# Tiny_Tetris_v1_3.net
KiCad netlist of a schematic drawn in EAGLE
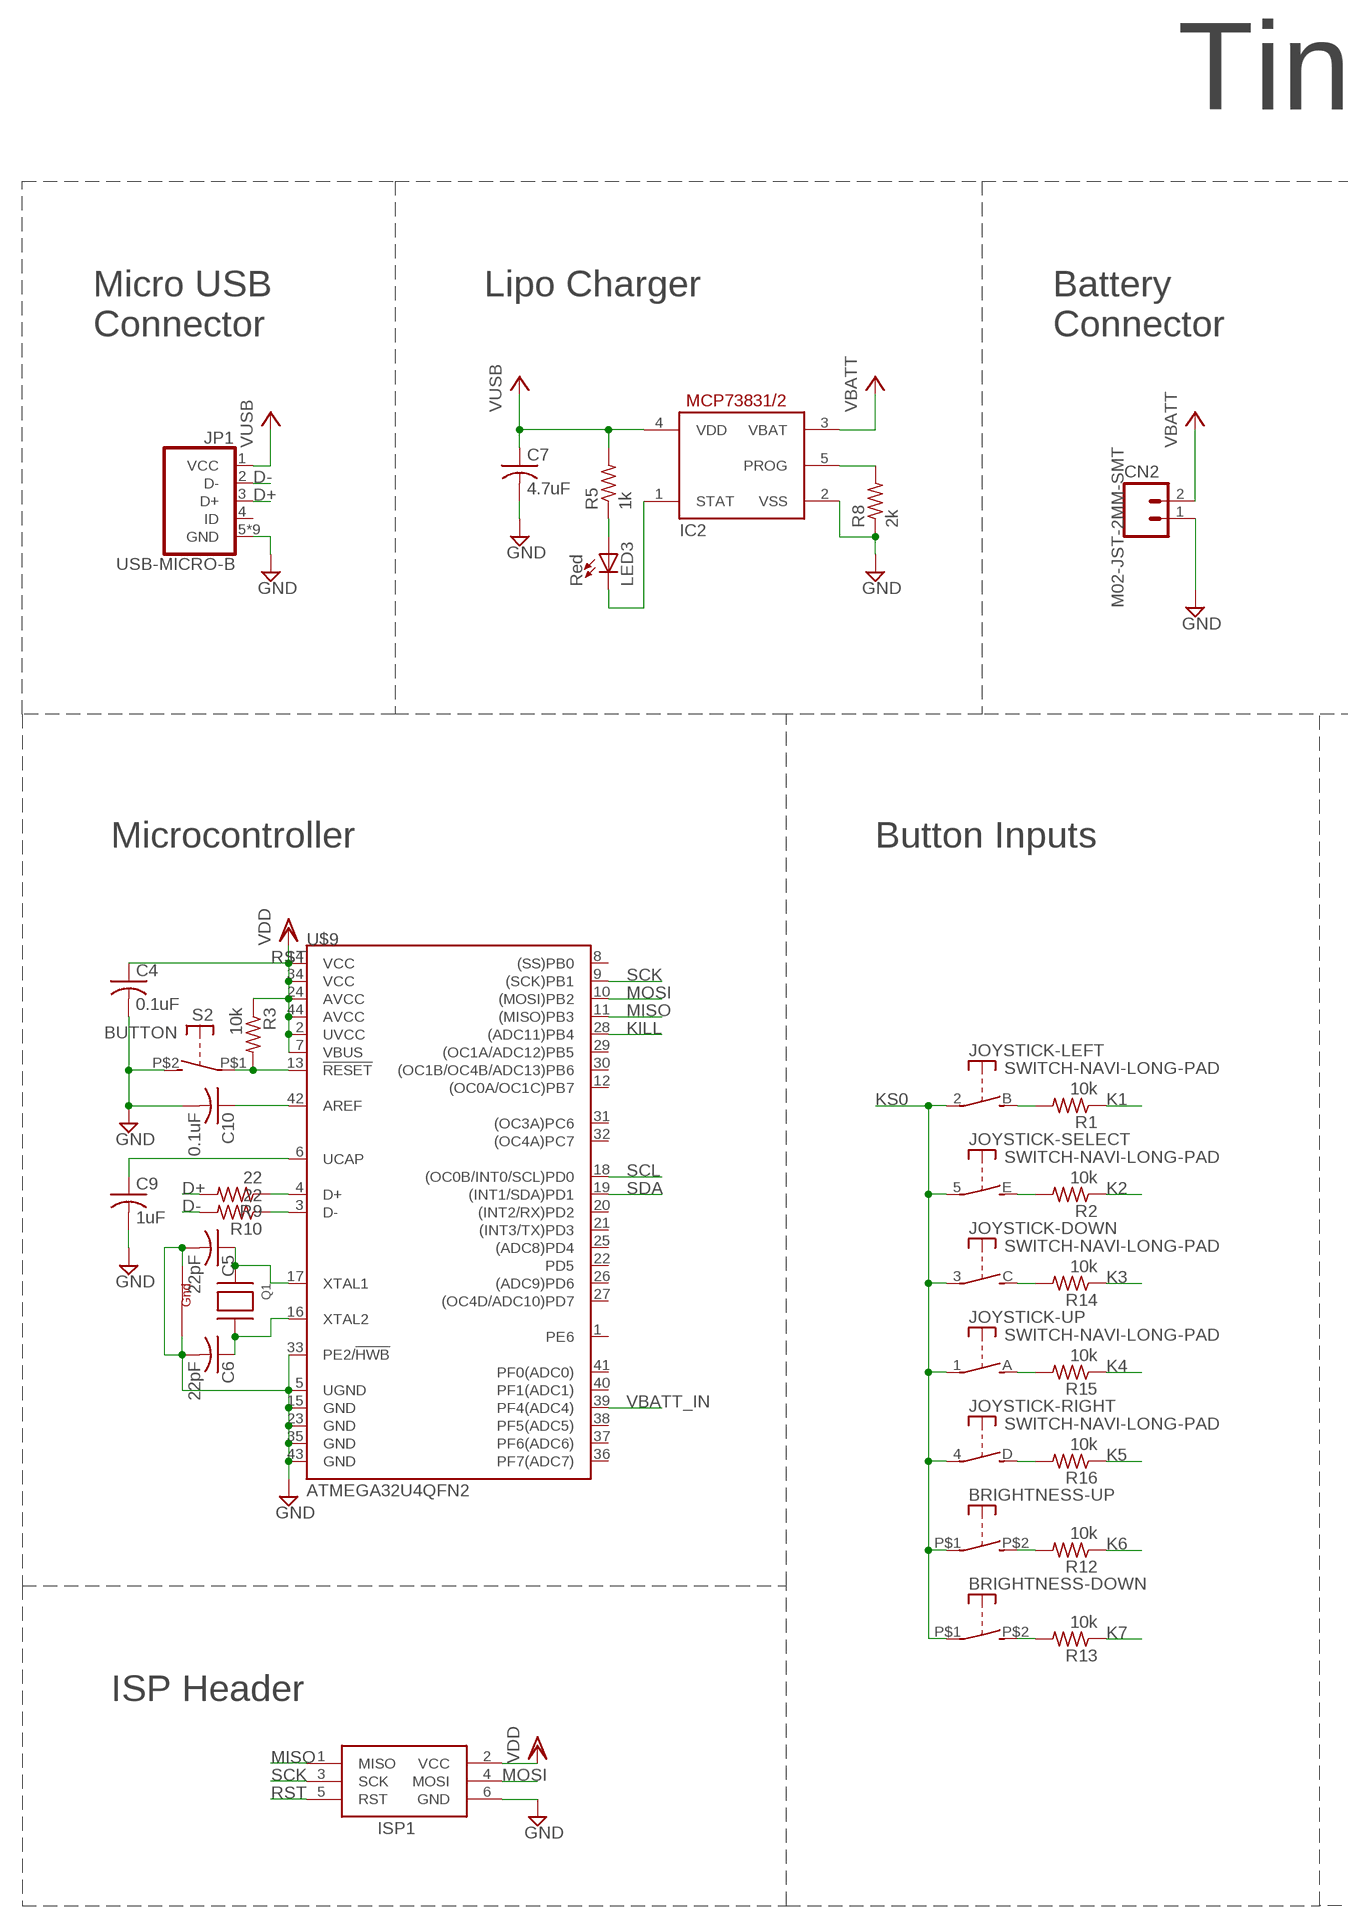
[diagram p0: schematic, sheet 1, part 1 of 2]
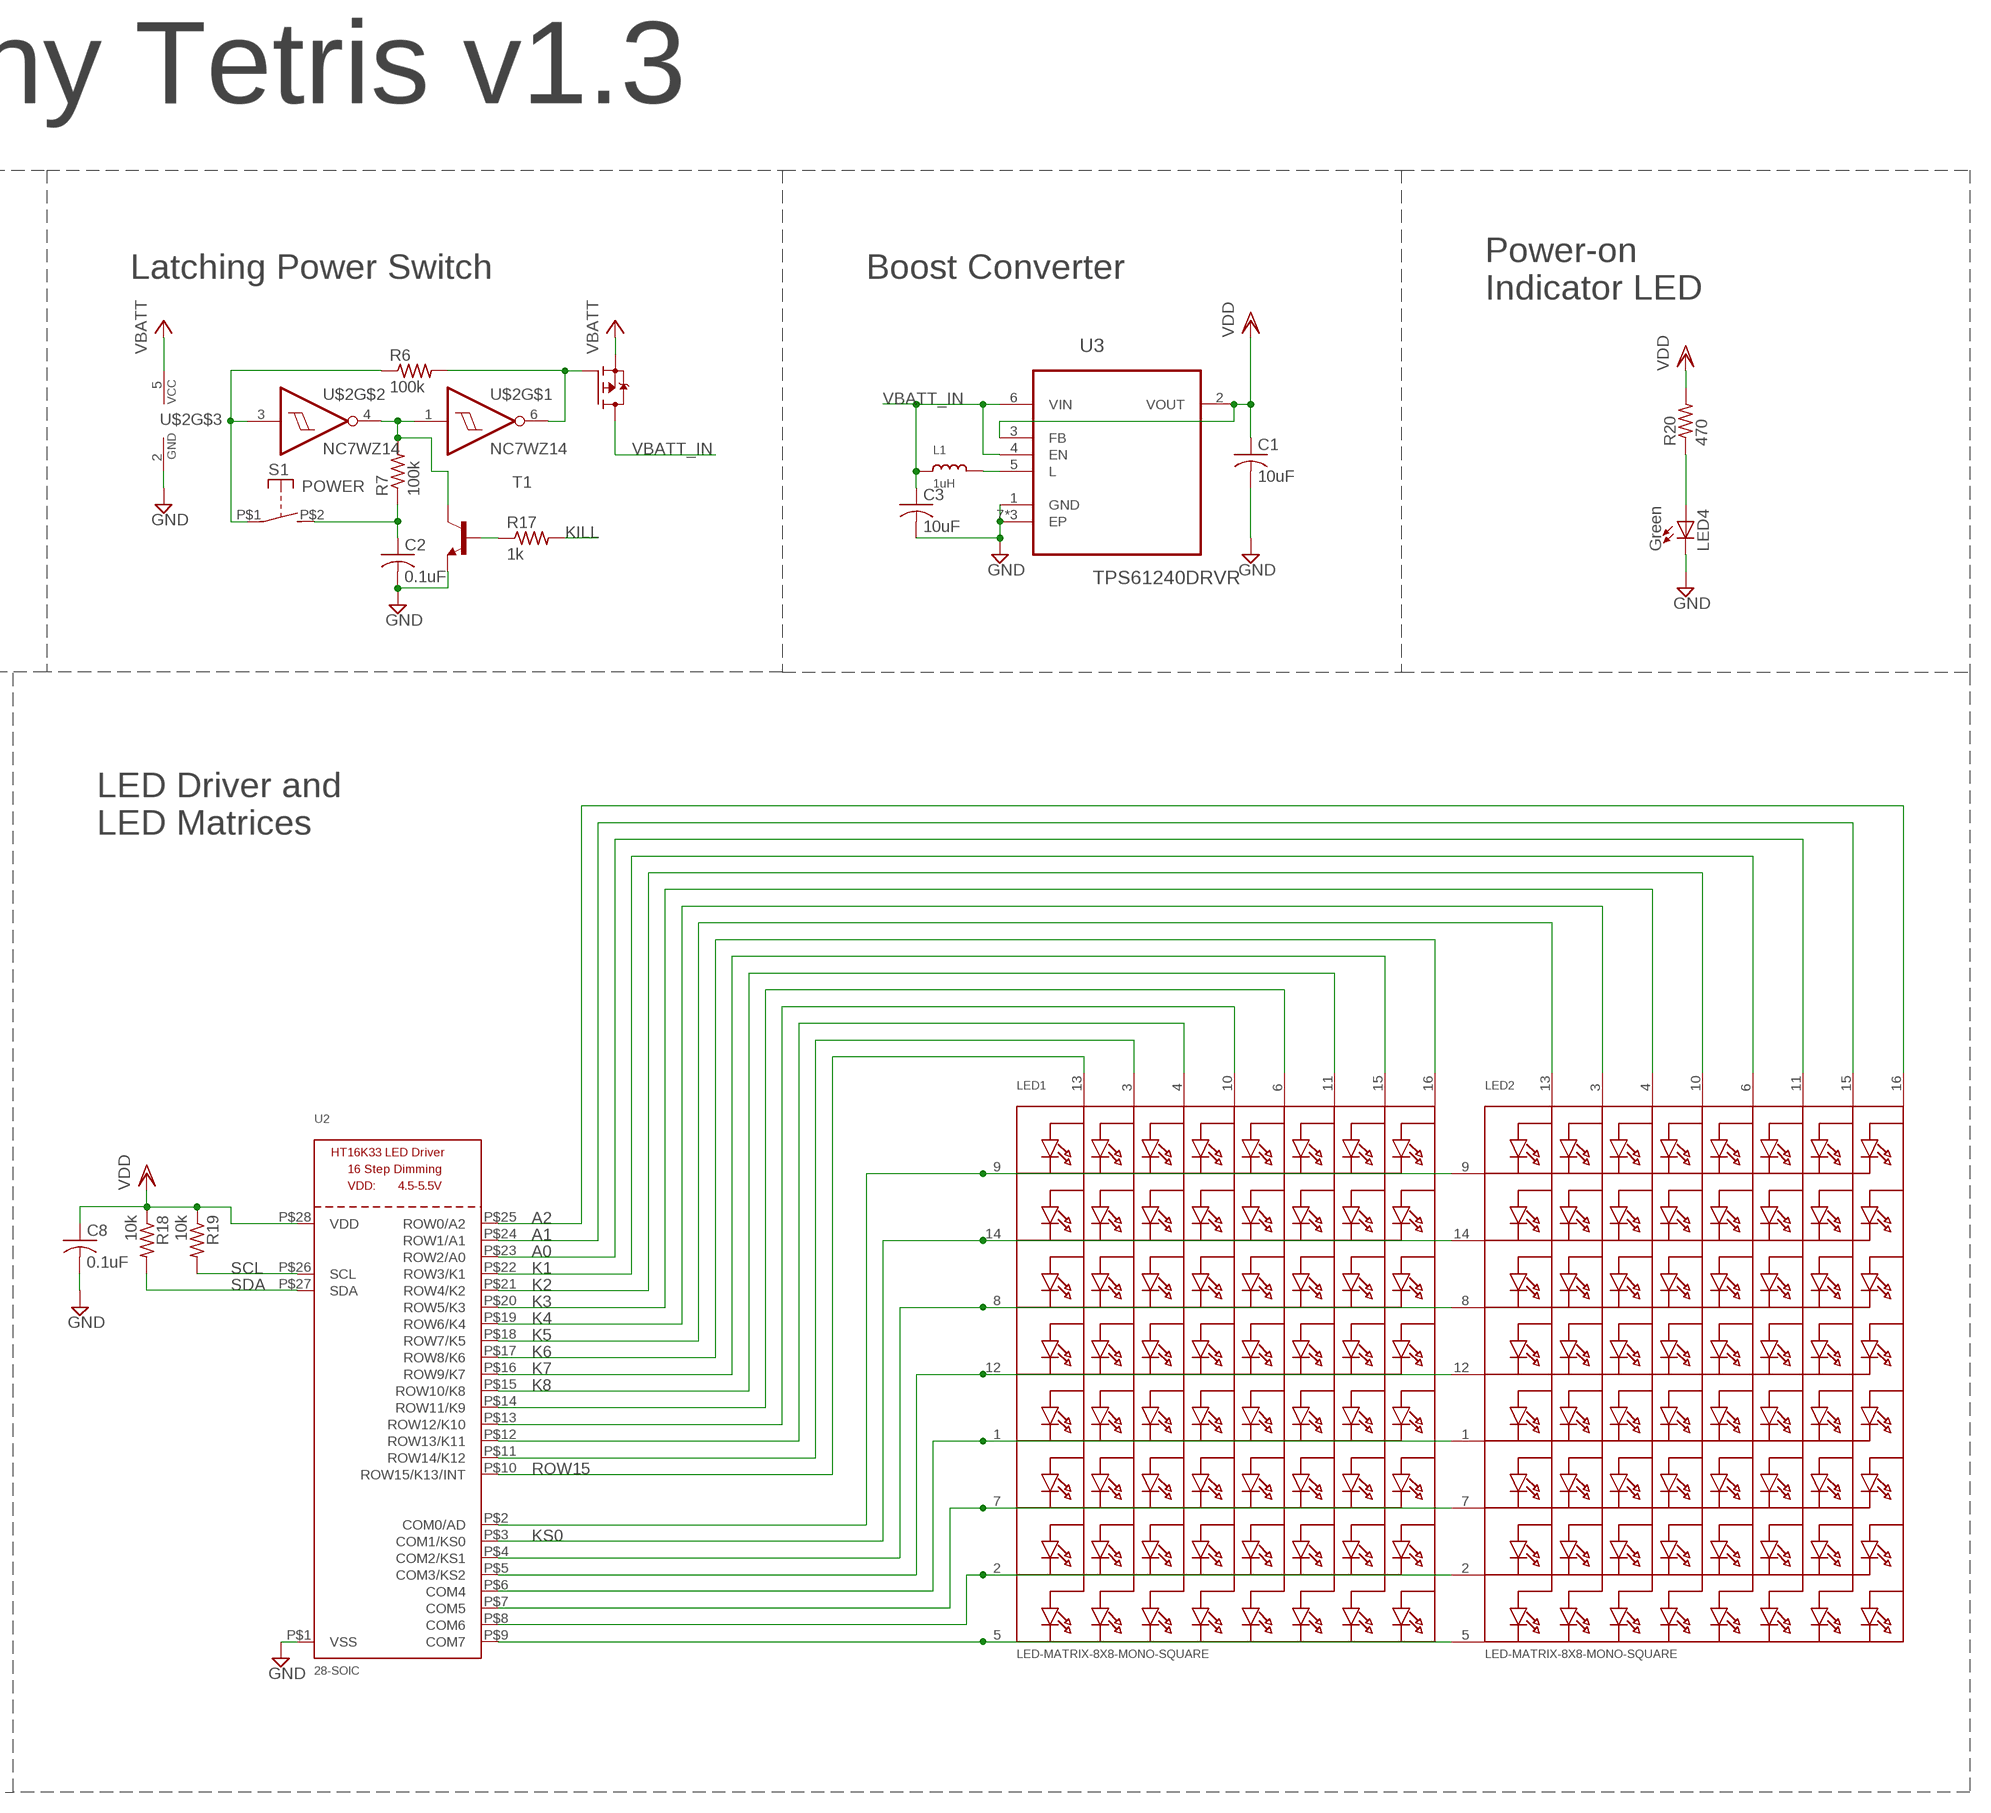
[diagram p1: schematic, sheet 1, part 2 of 2]

(export (version "E")
  (design (tool "Eeschema 10.0.6"))
  (components
    (comp (ref "BRIGHTNESS-DOWN")
      (value "SWITCH-TACTSKRELGE010")
      (footprint "eagle-import:TACT-ALPS-SKRELGE010")
      (libsource (lib "eagle-import") (part "SWITCH-TACTSKRELGE010"))
    )
    (comp (ref "BRIGHTNESS-UP")
      (value "SWITCH-TACTSKRELGE010")
      (footprint "eagle-import:TACT-ALPS-SKRELGE010")
      (libsource (lib "eagle-import") (part "SWITCH-TACTSKRELGE010"))
    )
    (comp (ref "C1")
      (value "10uF")
      (footprint "eagle-import:C0603K")
      (libsource (lib "eagle-import") (part "C-USC0603K"))
    )
    (comp (ref "C2")
      (value "0.1uF")
      (footprint "eagle-import:C0603K")
      (libsource (lib "eagle-import") (part "C-USC0603K"))
    )
    (comp (ref "C3")
      (value "10uF")
      (footprint "eagle-import:C0603K")
      (libsource (lib "eagle-import") (part "C-USC0603K"))
    )
    (comp (ref "C4")
      (value "0.1uF")
      (footprint "eagle-import:C0603K")
      (libsource (lib "eagle-import") (part "C-USC0603K"))
    )
    (comp (ref "C5")
      (value "22pF")
      (footprint "eagle-import:C0603K")
      (libsource (lib "eagle-import") (part "C-USC0603K"))
    )
    (comp (ref "C6")
      (value "22pF")
      (footprint "eagle-import:C0603K")
      (libsource (lib "eagle-import") (part "C-USC0603K"))
    )
    (comp (ref "C7")
      (value "4.7uF")
      (footprint "eagle-import:C0603K")
      (libsource (lib "eagle-import") (part "C-USC0603K"))
    )
    (comp (ref "C8")
      (value "0.1uF")
      (footprint "eagle-import:C0603K")
      (libsource (lib "eagle-import") (part "C-USC0603K"))
    )
    (comp (ref "C9")
      (value "1uF")
      (footprint "eagle-import:C0603K")
      (libsource (lib "eagle-import") (part "C-USC0603K"))
    )
    (comp (ref "C10")
      (value "0.1uF")
      (footprint "eagle-import:C0603K")
      (libsource (lib "eagle-import") (part "C-USC0603K"))
    )
    (comp (ref "CN2")
      (value "M02-JST-2MM-SMT")
      (footprint "eagle-import:1X02_NO_SILK")
      (libsource (lib "eagle-import") (part "M021X02_NO_SILK"))
    )
    (comp (ref "IC2")
      (value "MCP73831/OT")
      (footprint "eagle-import:SOT23-5L")
      (libsource (lib "eagle-import") (part "MCP73831/OT"))
    )
    (comp (ref "ISP1")
      (value "AVRISP-6")
      (footprint "eagle-import:AVRISP")
      (libsource (lib "eagle-import") (part "AVRISP-6"))
    )
    (comp (ref "JOYSTICK-")
      (value "SWITCH-NAVI-LONG-PAD")
      (footprint "eagle-import:JOYSTICK-NOKIA-3230-LONG-PAD")
      (libsource (lib "eagle-import") (part "SWITCH-NAVI-LONG-PAD"))
    )
    (comp (ref "JP1")
      (value "USB-MICRO-B")
      (footprint "eagle-import:MICRO-USB-FCI-10103594")
      (libsource (lib "eagle-import") (part "USB-MICRO-B"))
    )
    (comp (ref "L1")
      (value "1uH")
      (footprint "eagle-import:0805")
      (libsource (lib "eagle-import") (part "INDUCTOR0805"))
    )
    (comp (ref "LED1")
      (value "LED-MATRIX-8X8-MONO-SQUARE")
      (footprint "eagle-import:LED-MATRIX-8X8-MONO-SQUARE")
      (libsource (lib "eagle-import") (part "LED-MATRIX-8X8-MONO-SQUARE"))
    )
    (comp (ref "LED2")
      (value "LED-MATRIX-8X8-MONO-SQUARE")
      (footprint "eagle-import:LED-MATRIX-8X8-MONO-SQUARE")
      (libsource (lib "eagle-import") (part "LED-MATRIX-8X8-MONO-SQUARE"))
    )
    (comp (ref "LED3")
      (value "Red")
      (footprint "eagle-import:LED-0603-SIDEVIEW")
      (libsource (lib "eagle-import") (part "LED"))
    )
    (comp (ref "LED4")
      (value "Green")
      (footprint "eagle-import:LED-0603-SIDEVIEW")
      (libsource (lib "eagle-import") (part "LED"))
    )
    (comp (ref "Q1")
      (value "XTAL-4-3225")
      (footprint "eagle-import:NX3225")
      (libsource (lib "eagle-import") (part "XTAL-4-3225"))
    )
    (comp (ref "R1")
      (value "10k")
      (footprint "eagle-import:R0603")
      (libsource (lib "eagle-import") (part "R-US_R0603"))
    )
    (comp (ref "R2")
      (value "10k")
      (footprint "eagle-import:R0603")
      (libsource (lib "eagle-import") (part "R-US_R0603"))
    )
    (comp (ref "R3")
      (value "10k")
      (footprint "eagle-import:R0603")
      (libsource (lib "eagle-import") (part "R-US_R0603"))
    )
    (comp (ref "R5")
      (value "1k")
      (footprint "eagle-import:R0603")
      (libsource (lib "eagle-import") (part "R-US_R0603"))
    )
    (comp (ref "R6")
      (value "100k")
      (footprint "eagle-import:R0603")
      (libsource (lib "eagle-import") (part "R-US_R0603"))
    )
    (comp (ref "R7")
      (value "100k")
      (footprint "eagle-import:R0603")
      (libsource (lib "eagle-import") (part "R-US_R0603"))
    )
    (comp (ref "R8")
      (value "2k")
      (footprint "eagle-import:R0603")
      (libsource (lib "eagle-import") (part "R-US_R0603"))
    )
    (comp (ref "R9")
      (value "22")
      (footprint "eagle-import:R0603")
      (libsource (lib "eagle-import") (part "R-US_R0603"))
    )
    (comp (ref "R10")
      (value "22")
      (footprint "eagle-import:R0603")
      (libsource (lib "eagle-import") (part "R-US_R0603"))
    )
    (comp (ref "R12")
      (value "10k")
      (footprint "eagle-import:R0603")
      (libsource (lib "eagle-import") (part "R-US_R0603"))
    )
    (comp (ref "R13")
      (value "10k")
      (footprint "eagle-import:R0603")
      (libsource (lib "eagle-import") (part "R-US_R0603"))
    )
    (comp (ref "R14")
      (value "10k")
      (footprint "eagle-import:R0603")
      (libsource (lib "eagle-import") (part "R-US_R0603"))
    )
    (comp (ref "R15")
      (value "10k")
      (footprint "eagle-import:R0603")
      (libsource (lib "eagle-import") (part "R-US_R0603"))
    )
    (comp (ref "R16")
      (value "10k")
      (footprint "eagle-import:R0603")
      (libsource (lib "eagle-import") (part "R-US_R0603"))
    )
    (comp (ref "R17")
      (value "1k")
      (footprint "eagle-import:R0603")
      (libsource (lib "eagle-import") (part "R-US_R0603"))
    )
    (comp (ref "R18")
      (value "10k")
      (footprint "eagle-import:R0603")
      (libsource (lib "eagle-import") (part "R-US_R0603"))
    )
    (comp (ref "R19")
      (value "10k")
      (footprint "eagle-import:R0603")
      (libsource (lib "eagle-import") (part "R-US_R0603"))
    )
    (comp (ref "R20")
      (value "470")
      (footprint "eagle-import:R0603")
      (libsource (lib "eagle-import") (part "R-US_R0603"))
    )
    (comp (ref "S1")
      (value "POWER")
      (footprint "eagle-import:TACT-ALPS-SKRELGE010")
      (libsource (lib "eagle-import") (part "SWITCH-TACTSKRELGE010"))
    )
    (comp (ref "S2")
      (value "BUTTON")
      (footprint "eagle-import:TACT-ALPS-SKRELGE010")
      (libsource (lib "eagle-import") (part "SWITCH-TACTSKRELGE010"))
    )
    (comp (ref "T1")
      (value "MMBT2222ALT1-NPN-SOT23-BEC")
      (footprint "eagle-import:SOT23-BEC")
      (libsource (lib "eagle-import") (part "-NPN-SOT23-BECMMBT2222ALT1"))
    )
    (comp (ref "U$1")
      (value "IRLML6402")
      (footprint "eagle-import:SOT23")
      (libsource (lib "eagle-import") (part "IRLML6402"))
    )
    (comp (ref "U$2")
      (value "NC7WZ14")
      (footprint "eagle-import:SC-70-6")
      (libsource (lib "eagle-import") (part "NC7WZ14"))
    )
    (comp (ref "U$9")
      (value "ATMEGA32U4QFN2")
      (footprint "eagle-import:SPARKFUN-DIGITALIC_QFN-44-NOPAD")
      (libsource (lib "eagle-import") (part "ATMEGA32U4QFN2"))
    )
    (comp (ref "U2")
      (value "28-SOIC")
      (footprint "eagle-import:SOP28_300MIL")
      (libsource (lib "eagle-import") (part "HT16K33_SOP28"))
    )
    (comp (ref "U3")
      (value "TPS61240DRVR")
      (footprint "eagle-import:SON65P200X200X80-7N")
      (libsource (lib "eagle-import") (part "TPS61240DRVR"))
    )
  )
  (nets
    (net (code "1") (name "/A0") (class "Default")
      (node (ref "LED2") (pin "11") (pinfunction "A6_11") (pintype "bidirectional"))
      (node (ref "U2") (pin "P$23") (pinfunction "ROW2/A0_P$23") (pintype "bidirectional"))
    )
    (net (code "2") (name "/A1") (class "Default")
      (node (ref "LED2") (pin "15") (pinfunction "A7_15") (pintype "bidirectional"))
      (node (ref "U2") (pin "P$24") (pinfunction "ROW1/A1_P$24") (pintype "bidirectional"))
    )
    (net (code "3") (name "/A2") (class "Default")
      (node (ref "LED2") (pin "16") (pinfunction "A8_16") (pintype "bidirectional"))
      (node (ref "U2") (pin "P$25") (pinfunction "ROW0/A2_P$25") (pintype "bidirectional"))
    )
    (net (code "4") (name "/D+") (class "Default")
      (node (ref "JP1") (pin "3") (pinfunction "D+_3") (pintype "bidirectional"))
      (node (ref "R9") (pin "2") (pinfunction "2_2") (pintype "passive"))
    )
    (net (code "5") (name "/D-") (class "Default")
      (node (ref "JP1") (pin "2") (pinfunction "D-_2") (pintype "bidirectional"))
      (node (ref "R10") (pin "2") (pinfunction "2_2") (pintype "passive"))
    )
    (net (code "6") (name "/K1") (class "Default")
      (node (ref "LED2") (pin "6") (pinfunction "A5_6") (pintype "bidirectional"))
      (node (ref "R1") (pin "1") (pinfunction "1_1") (pintype "passive"))
      (node (ref "U2") (pin "P$22") (pinfunction "ROW3/K1_P$22") (pintype "bidirectional"))
    )
    (net (code "7") (name "/K2") (class "Default")
      (node (ref "LED2") (pin "10") (pinfunction "A4_10") (pintype "bidirectional"))
      (node (ref "R2") (pin "1") (pinfunction "1_1") (pintype "passive"))
      (node (ref "U2") (pin "P$21") (pinfunction "ROW4/K2_P$21") (pintype "bidirectional"))
    )
    (net (code "8") (name "/K3") (class "Default")
      (node (ref "LED2") (pin "4") (pinfunction "A3_4") (pintype "bidirectional"))
      (node (ref "R14") (pin "1") (pinfunction "1_1") (pintype "passive"))
      (node (ref "U2") (pin "P$20") (pinfunction "ROW5/K3_P$20") (pintype "bidirectional"))
    )
    (net (code "9") (name "/K4") (class "Default")
      (node (ref "LED2") (pin "3") (pinfunction "A2_3") (pintype "bidirectional"))
      (node (ref "R15") (pin "1") (pinfunction "1_1") (pintype "passive"))
      (node (ref "U2") (pin "P$19") (pinfunction "ROW6/K4_P$19") (pintype "bidirectional"))
    )
    (net (code "10") (name "/K5") (class "Default")
      (node (ref "LED2") (pin "13") (pinfunction "A1_13") (pintype "bidirectional"))
      (node (ref "R16") (pin "1") (pinfunction "1_1") (pintype "passive"))
      (node (ref "U2") (pin "P$18") (pinfunction "ROW7/K5_P$18") (pintype "bidirectional"))
    )
    (net (code "11") (name "/K6") (class "Default")
      (node (ref "LED1") (pin "16") (pinfunction "A8_16") (pintype "bidirectional"))
      (node (ref "R12") (pin "1") (pinfunction "1_1") (pintype "passive"))
      (node (ref "U2") (pin "P$17") (pinfunction "ROW8/K6_P$17") (pintype "bidirectional"))
    )
    (net (code "12") (name "/K7") (class "Default")
      (node (ref "LED1") (pin "15") (pinfunction "A7_15") (pintype "bidirectional"))
      (node (ref "R13") (pin "1") (pinfunction "1_1") (pintype "passive"))
      (node (ref "U2") (pin "P$16") (pinfunction "ROW9/K7_P$16") (pintype "bidirectional"))
    )
    (net (code "13") (name "/K8") (class "Default")
      (node (ref "LED1") (pin "11") (pinfunction "A6_11") (pintype "bidirectional"))
      (node (ref "U2") (pin "P$15") (pinfunction "ROW10/K8_P$15") (pintype "bidirectional"))
    )
    (net (code "14") (name "/KILL") (class "Default")
      (node (ref "R17") (pin "2") (pinfunction "2_2") (pintype "passive"))
      (node (ref "U$9") (pin "28") (pinfunction "(ADC11)PB4_28") (pintype "bidirectional"))
    )
    (net (code "15") (name "/KS0") (class "Default")
      (node (ref "BRIGHTNESS-DOWN") (pin "P$1") (pinfunction "P_P$1") (pintype "passive"))
      (node (ref "BRIGHTNESS-UP") (pin "P$1") (pinfunction "P_P$1") (pintype "passive"))
      (node (ref "JOYSTICK-") (pin "1") (pinfunction "P_1") (pintype "passive"))
      (node (ref "JOYSTICK-") (pin "2") (pinfunction "P_2") (pintype "passive"))
      (node (ref "JOYSTICK-") (pin "3") (pinfunction "P_3") (pintype "passive"))
      (node (ref "JOYSTICK-") (pin "4") (pinfunction "P_4") (pintype "passive"))
      (node (ref "JOYSTICK-") (pin "5") (pinfunction "P_5") (pintype "passive"))
      (node (ref "LED1") (pin "14") (pinfunction "K2_14") (pintype "bidirectional"))
      (node (ref "LED2") (pin "14") (pinfunction "K2_14") (pintype "bidirectional"))
      (node (ref "U2") (pin "P$3") (pinfunction "COM1/KS0_P$3") (pintype "bidirectional"))
    )
    (net (code "16") (name "/MISO") (class "Default")
      (node (ref "ISP1") (pin "1") (pinfunction "MISO_1") (pintype "input"))
      (node (ref "U$9") (pin "11") (pinfunction "(MISO)PB3_11") (pintype "bidirectional"))
    )
    (net (code "17") (name "/MOSI") (class "Default")
      (node (ref "ISP1") (pin "4") (pinfunction "MOSI_4") (pintype "output"))
      (node (ref "U$9") (pin "10") (pinfunction "(MOSI)PB2_10") (pintype "bidirectional"))
    )
    (net (code "18") (name "/ROW15") (class "Default")
      (node (ref "LED1") (pin "13") (pinfunction "A1_13") (pintype "bidirectional"))
      (node (ref "U2") (pin "P$10") (pinfunction "ROW15/K13/INT_P$10") (pintype "bidirectional"))
    )
    (net (code "19") (name "/RST") (class "Default")
      (node (ref "ISP1") (pin "5") (pinfunction "RST_5") (pintype "output"))
      (node (ref "R3") (pin "2") (pinfunction "2_2") (pintype "passive"))
      (node (ref "S2") (pin "P$1") (pinfunction "P_P$1") (pintype "passive"))
      (node (ref "U$9") (pin "13") (pinfunction "~{RESET}_13") (pintype "bidirectional"))
    )
    (net (code "20") (name "/SCK") (class "Default")
      (node (ref "ISP1") (pin "3") (pinfunction "SCK_3") (pintype "output"))
      (node (ref "U$9") (pin "9") (pinfunction "(SCK)PB1_9") (pintype "bidirectional"))
    )
    (net (code "21") (name "/SCL") (class "Default")
      (node (ref "R19") (pin "2") (pinfunction "2_2") (pintype "passive"))
      (node (ref "U$9") (pin "18") (pinfunction "(OC0B/INT0/SCL)PD0_18") (pintype "bidirectional"))
      (node (ref "U2") (pin "P$26") (pinfunction "SCL_P$26") (pintype "bidirectional"))
    )
    (net (code "22") (name "/SDA") (class "Default")
      (node (ref "R18") (pin "2") (pinfunction "2_2") (pintype "passive"))
      (node (ref "U$9") (pin "19") (pinfunction "(INT1/SDA)PD1_19") (pintype "bidirectional"))
      (node (ref "U2") (pin "P$27") (pinfunction "SDA_P$27") (pintype "bidirectional"))
    )
    (net (code "23") (name "/VBATT_IN") (class "Default")
      (node (ref "C3") (pin "1") (pinfunction "1_1") (pintype "passive"))
      (node (ref "L1") (pin "1") (pinfunction "1_1") (pintype "passive"))
      (node (ref "U$1") (pin "3") (pinfunction "D_3") (pintype "passive"))
      (node (ref "U$9") (pin "39") (pinfunction "PF4(ADC4)_39") (pintype "bidirectional"))
      (node (ref "U3") (pin "4") (pinfunction "EN_4") (pintype "input"))
      (node (ref "U3") (pin "6") (pinfunction "VIN_6") (pintype "power_in"))
    )
    (net (code "24") (name "GND") (class "Default")
      (node (ref "C1") (pin "2") (pinfunction "2_2") (pintype "passive"))
      (node (ref "C10") (pin "2") (pinfunction "2_2") (pintype "passive"))
      (node (ref "C2") (pin "2") (pinfunction "2_2") (pintype "passive"))
      (node (ref "C3") (pin "2") (pinfunction "2_2") (pintype "passive"))
      (node (ref "C4") (pin "2") (pinfunction "2_2") (pintype "passive"))
      (node (ref "C5") (pin "2") (pinfunction "2_2") (pintype "passive"))
      (node (ref "C6") (pin "2") (pinfunction "2_2") (pintype "passive"))
      (node (ref "C7") (pin "2") (pinfunction "2_2") (pintype "passive"))
      (node (ref "C8") (pin "2") (pinfunction "2_2") (pintype "passive"))
      (node (ref "C9") (pin "2") (pinfunction "2_2") (pintype "passive"))
      (node (ref "CN2") (pin "1") (pinfunction "1_1") (pintype "passive"))
      (node (ref "IC2") (pin "2") (pinfunction "VSS_2") (pintype "power_in"))
      (node (ref "ISP1") (pin "6") (pinfunction "GND_6") (pintype "power_in"))
      (node (ref "JP1") (pin "5") (pinfunction "GND_5") (pintype "bidirectional"))
      (node (ref "JP1") (pin "P$1") (pinfunction "GND_P$1") (pintype "bidirectional"))
      (node (ref "JP1") (pin "P$2") (pinfunction "GND_P$2") (pintype "bidirectional"))
      (node (ref "JP1") (pin "P$3") (pinfunction "GND_P$3") (pintype "bidirectional"))
      (node (ref "JP1") (pin "P$4") (pinfunction "GND_P$4") (pintype "bidirectional"))
      (node (ref "JP1") (pin "P$5") (pinfunction "GND_P$5") (pintype "bidirectional"))
      (node (ref "JP1") (pin "P$6") (pinfunction "GND_P$6") (pintype "bidirectional"))
      (node (ref "JP1") (pin "P$7") (pinfunction "GND_P$7") (pintype "bidirectional"))
      (node (ref "JP1") (pin "P$8") (pinfunction "GND_P$8") (pintype "bidirectional"))
      (node (ref "LED4") (pin "P$2") (pinfunction "C_P$2") (pintype "passive"))
      (node (ref "Q1") (pin "2") (pinfunction "G2_2") (pintype "power_in"))
      (node (ref "Q1") (pin "4") (pinfunction "G1_4") (pintype "power_in"))
      (node (ref "R8") (pin "1") (pinfunction "1_1") (pintype "passive"))
      (node (ref "S2") (pin "P$2") (pinfunction "S_P$2") (pintype "passive"))
      (node (ref "T1") (pin "E") (pinfunction "E_E") (pintype "passive"))
      (node (ref "U$2") (pin "2") (pinfunction "GND_2") (pintype "power_in"))
      (node (ref "U$9") (pin "15") (pinfunction "GND_15") (pintype "bidirectional"))
      (node (ref "U$9") (pin "23") (pinfunction "GND_23") (pintype "bidirectional"))
      (node (ref "U$9") (pin "33") (pinfunction "PE2/~{HWB}_33") (pintype "bidirectional"))
      (node (ref "U$9") (pin "35") (pinfunction "GND_35") (pintype "bidirectional"))
      (node (ref "U$9") (pin "43") (pinfunction "GND_43") (pintype "bidirectional"))
      (node (ref "U$9") (pin "5") (pinfunction "UGND_5") (pintype "bidirectional"))
      (node (ref "U2") (pin "P$1") (pinfunction "VSS_P$1") (pintype "bidirectional"))
      (node (ref "U3") (pin "1") (pinfunction "GND_1") (pintype "passive"))
      (node (ref "U3") (pin "7") (pinfunction "EP_7") (pintype "passive"))
      (node (ref "U3") (pin "8") (pinfunction "EP_8") (pintype "passive"))
      (node (ref "U3") (pin "9") (pinfunction "EP_9") (pintype "passive"))
    )
    (net (code "25") (name "Net-(BRIGHTNESS-DOWN-S)") (class "Default")
      (node (ref "BRIGHTNESS-DOWN") (pin "P$2") (pinfunction "S_P$2") (pintype "passive"))
      (node (ref "R13") (pin "2") (pinfunction "2_2") (pintype "passive"))
    )
    (net (code "26") (name "Net-(BRIGHTNESS-UP-S)") (class "Default")
      (node (ref "BRIGHTNESS-UP") (pin "P$2") (pinfunction "S_P$2") (pintype "passive"))
      (node (ref "R12") (pin "2") (pinfunction "2_2") (pintype "passive"))
    )
    (net (code "27") (name "Net-(IC2-PROG)") (class "Default")
      (node (ref "IC2") (pin "5") (pinfunction "PROG_5") (pintype "input"))
      (node (ref "R8") (pin "2") (pinfunction "2_2") (pintype "passive"))
    )
    (net (code "28") (name "Net-(IC2-STAT)") (class "Default")
      (node (ref "IC2") (pin "1") (pinfunction "STAT_1") (pintype "output"))
      (node (ref "LED3") (pin "P$2") (pinfunction "C_P$2") (pintype "passive"))
    )
    (net (code "29") (name "Net-(JOYSTICK-A-S)") (class "Default")
      (node (ref "JOYSTICK-") (pin "C") (pinfunction "S_C") (pintype "passive"))
      (node (ref "R14") (pin "2") (pinfunction "2_2") (pintype "passive"))
    )
    (net (code "30") (name "Net-(JOYSTICK-B-S)") (class "Default")
      (node (ref "JOYSTICK-") (pin "B") (pinfunction "S_B") (pintype "passive"))
      (node (ref "R1") (pin "2") (pinfunction "2_2") (pintype "passive"))
    )
    (net (code "31") (name "Net-(JOYSTICK-C-S)") (class "Default")
      (node (ref "JOYSTICK-") (pin "D") (pinfunction "S_D") (pintype "passive"))
      (node (ref "R16") (pin "2") (pinfunction "2_2") (pintype "passive"))
    )
    (net (code "32") (name "Net-(JOYSTICK-D-S)") (class "Default")
      (node (ref "JOYSTICK-") (pin "E") (pinfunction "S_E") (pintype "passive"))
      (node (ref "R2") (pin "2") (pinfunction "2_2") (pintype "passive"))
    )
    (net (code "33") (name "Net-(JOYSTICK-E-S)") (class "Default")
      (node (ref "JOYSTICK-") (pin "A") (pinfunction "S_A") (pintype "passive"))
      (node (ref "R15") (pin "2") (pinfunction "2_2") (pintype "passive"))
    )
    (net (code "34") (name "Net-(LED1-A2)") (class "Default")
      (node (ref "LED1") (pin "3") (pinfunction "A2_3") (pintype "bidirectional"))
      (node (ref "U2") (pin "P$11") (pinfunction "ROW14/K12_P$11") (pintype "bidirectional"))
    )
    (net (code "35") (name "Net-(LED1-A3)") (class "Default")
      (node (ref "LED1") (pin "4") (pinfunction "A3_4") (pintype "bidirectional"))
      (node (ref "U2") (pin "P$12") (pinfunction "ROW13/K11_P$12") (pintype "bidirectional"))
    )
    (net (code "36") (name "Net-(LED1-A4)") (class "Default")
      (node (ref "LED1") (pin "10") (pinfunction "A4_10") (pintype "bidirectional"))
      (node (ref "U2") (pin "P$13") (pinfunction "ROW12/K10_P$13") (pintype "bidirectional"))
    )
    (net (code "37") (name "Net-(LED1-A5)") (class "Default")
      (node (ref "LED1") (pin "6") (pinfunction "A5_6") (pintype "bidirectional"))
      (node (ref "U2") (pin "P$14") (pinfunction "ROW11/K9_P$14") (pintype "bidirectional"))
    )
    (net (code "38") (name "Net-(LED1-K1)") (class "Default")
      (node (ref "LED1") (pin "9") (pinfunction "K1_9") (pintype "bidirectional"))
      (node (ref "LED2") (pin "9") (pinfunction "K1_9") (pintype "bidirectional"))
      (node (ref "U2") (pin "P$2") (pinfunction "COM0/AD_P$2") (pintype "bidirectional"))
    )
    (net (code "39") (name "Net-(LED1-K3)") (class "Default")
      (node (ref "LED1") (pin "8") (pinfunction "K3_8") (pintype "bidirectional"))
      (node (ref "LED2") (pin "8") (pinfunction "K3_8") (pintype "bidirectional"))
      (node (ref "U2") (pin "P$4") (pinfunction "COM2/KS1_P$4") (pintype "bidirectional"))
    )
    (net (code "40") (name "Net-(LED1-K4)") (class "Default")
      (node (ref "LED1") (pin "12") (pinfunction "K4_12") (pintype "bidirectional"))
      (node (ref "LED2") (pin "12") (pinfunction "K4_12") (pintype "bidirectional"))
      (node (ref "U2") (pin "P$5") (pinfunction "COM3/KS2_P$5") (pintype "bidirectional"))
    )
    (net (code "41") (name "Net-(LED1-K5)") (class "Default")
      (node (ref "LED1") (pin "1") (pinfunction "K5_1") (pintype "bidirectional"))
      (node (ref "LED2") (pin "1") (pinfunction "K5_1") (pintype "bidirectional"))
      (node (ref "U2") (pin "P$6") (pinfunction "COM4_P$6") (pintype "bidirectional"))
    )
    (net (code "42") (name "Net-(LED1-K6)") (class "Default")
      (node (ref "LED1") (pin "7") (pinfunction "K6_7") (pintype "bidirectional"))
      (node (ref "LED2") (pin "7") (pinfunction "K6_7") (pintype "bidirectional"))
      (node (ref "U2") (pin "P$7") (pinfunction "COM5_P$7") (pintype "bidirectional"))
    )
    (net (code "43") (name "Net-(LED1-K7)") (class "Default")
      (node (ref "LED1") (pin "2") (pinfunction "K7_2") (pintype "bidirectional"))
      (node (ref "LED2") (pin "2") (pinfunction "K7_2") (pintype "bidirectional"))
      (node (ref "U2") (pin "P$8") (pinfunction "COM6_P$8") (pintype "bidirectional"))
    )
    (net (code "44") (name "Net-(LED1-K8)") (class "Default")
      (node (ref "LED1") (pin "5") (pinfunction "K8_5") (pintype "bidirectional"))
      (node (ref "LED2") (pin "5") (pinfunction "K8_5") (pintype "bidirectional"))
      (node (ref "U2") (pin "P$9") (pinfunction "COM7_P$9") (pintype "bidirectional"))
    )
    (net (code "45") (name "Net-(LED3-A)") (class "Default")
      (node (ref "LED3") (pin "P$1") (pinfunction "A_P$1") (pintype "passive"))
      (node (ref "R5") (pin "1") (pinfunction "1_1") (pintype "passive"))
    )
    (net (code "46") (name "Net-(LED4-A)") (class "Default")
      (node (ref "LED4") (pin "P$1") (pinfunction "A_P$1") (pintype "passive"))
      (node (ref "R20") (pin "1") (pinfunction "1_1") (pintype "passive"))
    )
    (net (code "47") (name "Net-(Q1-X1)") (class "Default")
      (node (ref "C5") (pin "1") (pinfunction "1_1") (pintype "passive"))
      (node (ref "Q1") (pin "1") (pinfunction "X1_1") (pintype "bidirectional"))
      (node (ref "U$9") (pin "17") (pinfunction "XTAL1_17") (pintype "bidirectional"))
    )
    (net (code "48") (name "Net-(Q1-X2)") (class "Default")
      (node (ref "C6") (pin "1") (pinfunction "1_1") (pintype "passive"))
      (node (ref "Q1") (pin "3") (pinfunction "X2_3") (pintype "bidirectional"))
      (node (ref "U$9") (pin "16") (pinfunction "XTAL2_16") (pintype "bidirectional"))
    )
    (net (code "49") (name "Net-(R17-Pad1)") (class "Default")
      (node (ref "R17") (pin "1") (pinfunction "1_1") (pintype "passive"))
      (node (ref "T1") (pin "B") (pinfunction "B_B") (pintype "passive"))
    )
    (net (code "50") (name "Net-(S1-P)") (class "Default")
      (node (ref "R6") (pin "1") (pinfunction "1_1") (pintype "passive"))
      (node (ref "S1") (pin "P$1") (pinfunction "P_P$1") (pintype "passive"))
      (node (ref "U$2") (pin "3") (pinfunction "I_3") (pintype "input"))
    )
    (net (code "51") (name "Net-(S1-S)") (class "Default")
      (node (ref "C2") (pin "1") (pinfunction "1_1") (pintype "passive"))
      (node (ref "R7") (pin "1") (pinfunction "1_1") (pintype "passive"))
      (node (ref "S1") (pin "P$2") (pinfunction "S_P$2") (pintype "passive"))
    )
    (net (code "52") (name "Net-(U$1-G)") (class "Default")
      (node (ref "R6") (pin "2") (pinfunction "2_2") (pintype "passive"))
      (node (ref "U$1") (pin "1") (pinfunction "G_1") (pintype "passive"))
      (node (ref "U$2") (pin "6") (pinfunction "O_6") (pintype "output"))
    )
    (net (code "53") (name "Net-(U$2A-I)") (class "Default")
      (node (ref "R7") (pin "2") (pinfunction "2_2") (pintype "passive"))
      (node (ref "T1") (pin "C") (pinfunction "C_C") (pintype "passive"))
      (node (ref "U$2") (pin "1") (pinfunction "I_1") (pintype "input"))
      (node (ref "U$2") (pin "4") (pinfunction "O_4") (pintype "output"))
    )
    (net (code "54") (name "Net-(U$9-AREF)") (class "Default")
      (node (ref "C10") (pin "1") (pinfunction "1_1") (pintype "passive"))
      (node (ref "U$9") (pin "42") (pinfunction "AREF_42") (pintype "bidirectional"))
    )
    (net (code "55") (name "Net-(U$9-D+)") (class "Default")
      (node (ref "R9") (pin "1") (pinfunction "1_1") (pintype "passive"))
      (node (ref "U$9") (pin "4") (pinfunction "D+_4") (pintype "bidirectional"))
    )
    (net (code "56") (name "Net-(U$9-D-)") (class "Default")
      (node (ref "R10") (pin "1") (pinfunction "1_1") (pintype "passive"))
      (node (ref "U$9") (pin "3") (pinfunction "D-_3") (pintype "bidirectional"))
    )
    (net (code "57") (name "Net-(U$9-UCAP)") (class "Default")
      (node (ref "C9") (pin "1") (pinfunction "1_1") (pintype "passive"))
      (node (ref "U$9") (pin "6") (pinfunction "UCAP_6") (pintype "bidirectional"))
    )
    (net (code "58") (name "Net-(U3-L)") (class "Default")
      (node (ref "L1") (pin "2") (pinfunction "2_2") (pintype "passive"))
      (node (ref "U3") (pin "5") (pinfunction "L_5") (pintype "input"))
    )
    (net (code "59") (name "VBATT") (class "Default")
      (node (ref "CN2") (pin "2") (pinfunction "2_2") (pintype "passive"))
      (node (ref "IC2") (pin "3") (pinfunction "VBAT_3") (pintype "bidirectional"))
      (node (ref "U$1") (pin "2") (pinfunction "S_2") (pintype "passive"))
      (node (ref "U$2") (pin "5") (pinfunction "VCC_5") (pintype "power_in"))
    )
    (net (code "60") (name "VDD") (class "Default")
      (node (ref "C1") (pin "1") (pinfunction "1_1") (pintype "passive"))
      (node (ref "C4") (pin "1") (pinfunction "1_1") (pintype "passive"))
      (node (ref "C8") (pin "1") (pinfunction "1_1") (pintype "passive"))
      (node (ref "ISP1") (pin "2") (pinfunction "VCC_2") (pintype "power_in"))
      (node (ref "R18") (pin "1") (pinfunction "1_1") (pintype "passive"))
      (node (ref "R19") (pin "1") (pinfunction "1_1") (pintype "passive"))
      (node (ref "R20") (pin "2") (pinfunction "2_2") (pintype "passive"))
      (node (ref "R3") (pin "1") (pinfunction "1_1") (pintype "passive"))
      (node (ref "U$9") (pin "14") (pinfunction "VCC_14") (pintype "bidirectional"))
      (node (ref "U$9") (pin "2") (pinfunction "UVCC_2") (pintype "bidirectional"))
      (node (ref "U$9") (pin "24") (pinfunction "AVCC_24") (pintype "bidirectional"))
      (node (ref "U$9") (pin "34") (pinfunction "VCC_34") (pintype "bidirectional"))
      (node (ref "U$9") (pin "44") (pinfunction "AVCC_44") (pintype "bidirectional"))
      (node (ref "U$9") (pin "7") (pinfunction "VBUS_7") (pintype "bidirectional"))
      (node (ref "U2") (pin "P$28") (pinfunction "VDD_P$28") (pintype "bidirectional"))
      (node (ref "U3") (pin "2") (pinfunction "VOUT_2") (pintype "power_in"))
      (node (ref "U3") (pin "3") (pinfunction "FB_3") (pintype "input"))
    )
    (net (code "61") (name "VUSB") (class "Default")
      (node (ref "C7") (pin "1") (pinfunction "1_1") (pintype "passive"))
      (node (ref "IC2") (pin "4") (pinfunction "VDD_4") (pintype "power_in"))
      (node (ref "JP1") (pin "1") (pinfunction "VCC_1") (pintype "bidirectional"))
      (node (ref "R5") (pin "2") (pinfunction "2_2") (pintype "passive"))
    )
    (net (code "62") (name "unconnected-(JP1-ID-Pad4)") (class "Default")
      (node (ref "JP1") (pin "4") (pinfunction "ID_4") (pintype "bidirectional"))
    )
    (net (code "63") (name "unconnected-(U$9-(ADC8)PD4-Pad25)") (class "Default")
      (node (ref "U$9") (pin "25") (pinfunction "(ADC8)PD4_25") (pintype "bidirectional"))
    )
    (net (code "64") (name "unconnected-(U$9-(ADC9)PD6-Pad26)") (class "Default")
      (node (ref "U$9") (pin "26") (pinfunction "(ADC9)PD6_26") (pintype "bidirectional"))
    )
    (net (code "65") (name "unconnected-(U$9-(INT2{slash}RX)PD2-Pad20)") (class "Default")
      (node (ref "U$9") (pin "20") (pinfunction "(INT2/RX)PD2_20") (pintype "bidirectional"))
    )
    (net (code "66") (name "unconnected-(U$9-(INT3{slash}TX)PD3-Pad21)") (class "Default")
      (node (ref "U$9") (pin "21") (pinfunction "(INT3/TX)PD3_21") (pintype "bidirectional"))
    )
    (net (code "67") (name "unconnected-(U$9-(OC0A{slash}OC1C)PB7-Pad12)") (class "Default")
      (node (ref "U$9") (pin "12") (pinfunction "(OC0A/OC1C)PB7_12") (pintype "bidirectional"))
    )
    (net (code "68") (name "unconnected-(U$9-(OC1A{slash}ADC12)PB5-Pad29)") (class "Default")
      (node (ref "U$9") (pin "29") (pinfunction "(OC1A/ADC12)PB5_29") (pintype "bidirectional"))
    )
    (net (code "69") (name "unconnected-(U$9-(OC1B{slash}OC4B{slash}ADC13)PB6-Pad30)") (class "Default")
      (node (ref "U$9") (pin "30") (pinfunction "(OC1B/OC4B/ADC13)PB6_30") (pintype "bidirectional"))
    )
    (net (code "70") (name "unconnected-(U$9-(OC3A)PC6-Pad31)") (class "Default")
      (node (ref "U$9") (pin "31") (pinfunction "(OC3A)PC6_31") (pintype "bidirectional"))
    )
    (net (code "71") (name "unconnected-(U$9-(OC4A)PC7-Pad32)") (class "Default")
      (node (ref "U$9") (pin "32") (pinfunction "(OC4A)PC7_32") (pintype "bidirectional"))
    )
    (net (code "72") (name "unconnected-(U$9-(OC4D{slash}ADC10)PD7-Pad27)") (class "Default")
      (node (ref "U$9") (pin "27") (pinfunction "(OC4D/ADC10)PD7_27") (pintype "bidirectional"))
    )
    (net (code "73") (name "unconnected-(U$9-(SS)PB0-Pad8)") (class "Default")
      (node (ref "U$9") (pin "8") (pinfunction "(SS)PB0_8") (pintype "bidirectional"))
    )
    (net (code "74") (name "unconnected-(U$9-PD5-Pad22)") (class "Default")
      (node (ref "U$9") (pin "22") (pinfunction "PD5_22") (pintype "bidirectional"))
    )
    (net (code "75") (name "unconnected-(U$9-PE6-Pad1)") (class "Default")
      (node (ref "U$9") (pin "1") (pinfunction "PE6_1") (pintype "bidirectional"))
    )
    (net (code "76") (name "unconnected-(U$9-PF0(ADC0)-Pad41)") (class "Default")
      (node (ref "U$9") (pin "41") (pinfunction "PF0(ADC0)_41") (pintype "bidirectional"))
    )
    (net (code "77") (name "unconnected-(U$9-PF1(ADC1)-Pad40)") (class "Default")
      (node (ref "U$9") (pin "40") (pinfunction "PF1(ADC1)_40") (pintype "bidirectional"))
    )
    (net (code "78") (name "unconnected-(U$9-PF5(ADC5)-Pad38)") (class "Default")
      (node (ref "U$9") (pin "38") (pinfunction "PF5(ADC5)_38") (pintype "bidirectional"))
    )
    (net (code "79") (name "unconnected-(U$9-PF6(ADC6)-Pad37)") (class "Default")
      (node (ref "U$9") (pin "37") (pinfunction "PF6(ADC6)_37") (pintype "bidirectional"))
    )
    (net (code "80") (name "unconnected-(U$9-PF7(ADC7)-Pad36)") (class "Default")
      (node (ref "U$9") (pin "36") (pinfunction "PF7(ADC7)_36") (pintype "bidirectional"))
    )
  )
)
